# Hank.net
KiCad netlist of a schematic drawn in EAGLE
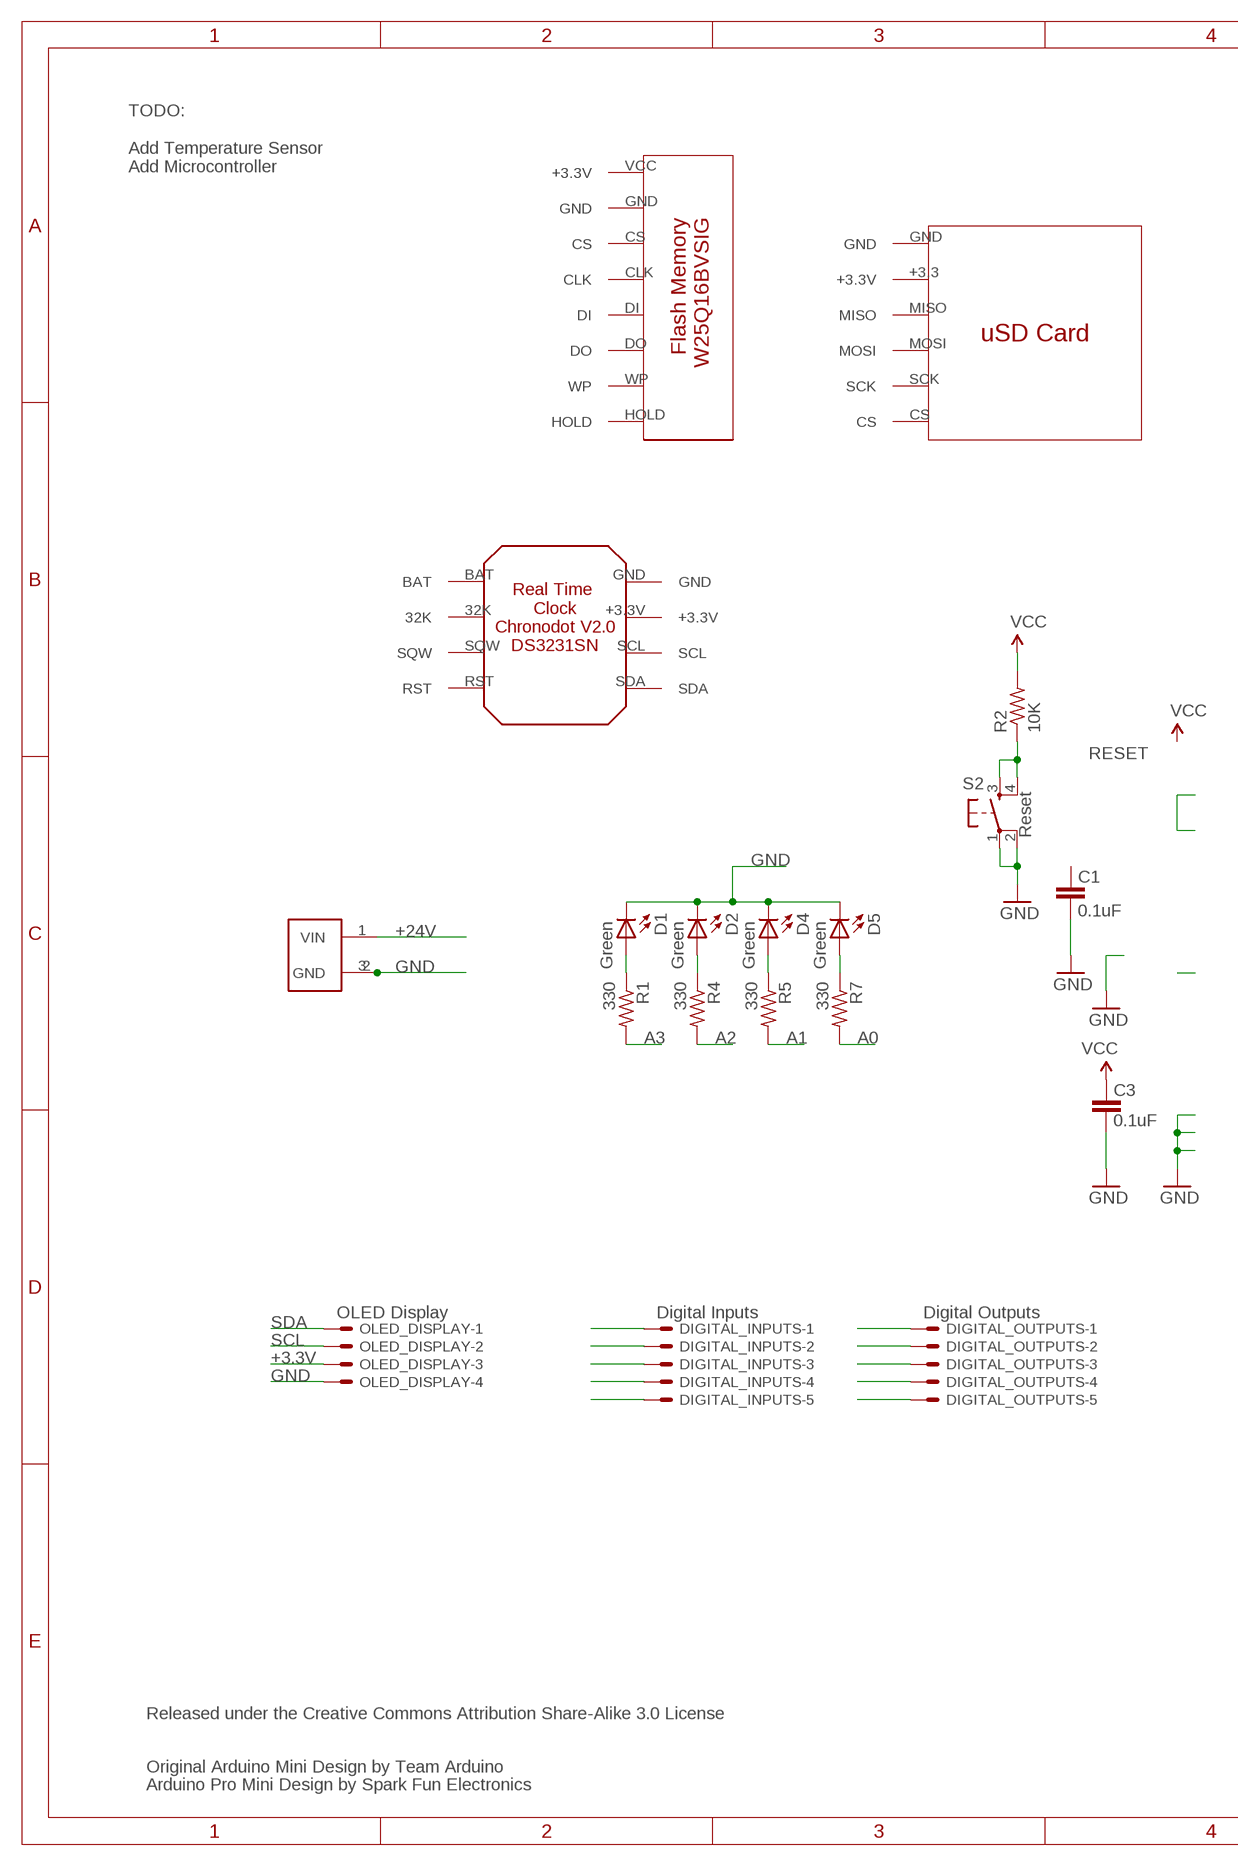
[diagram p0: schematic, sheet 1, part 1 of 2]
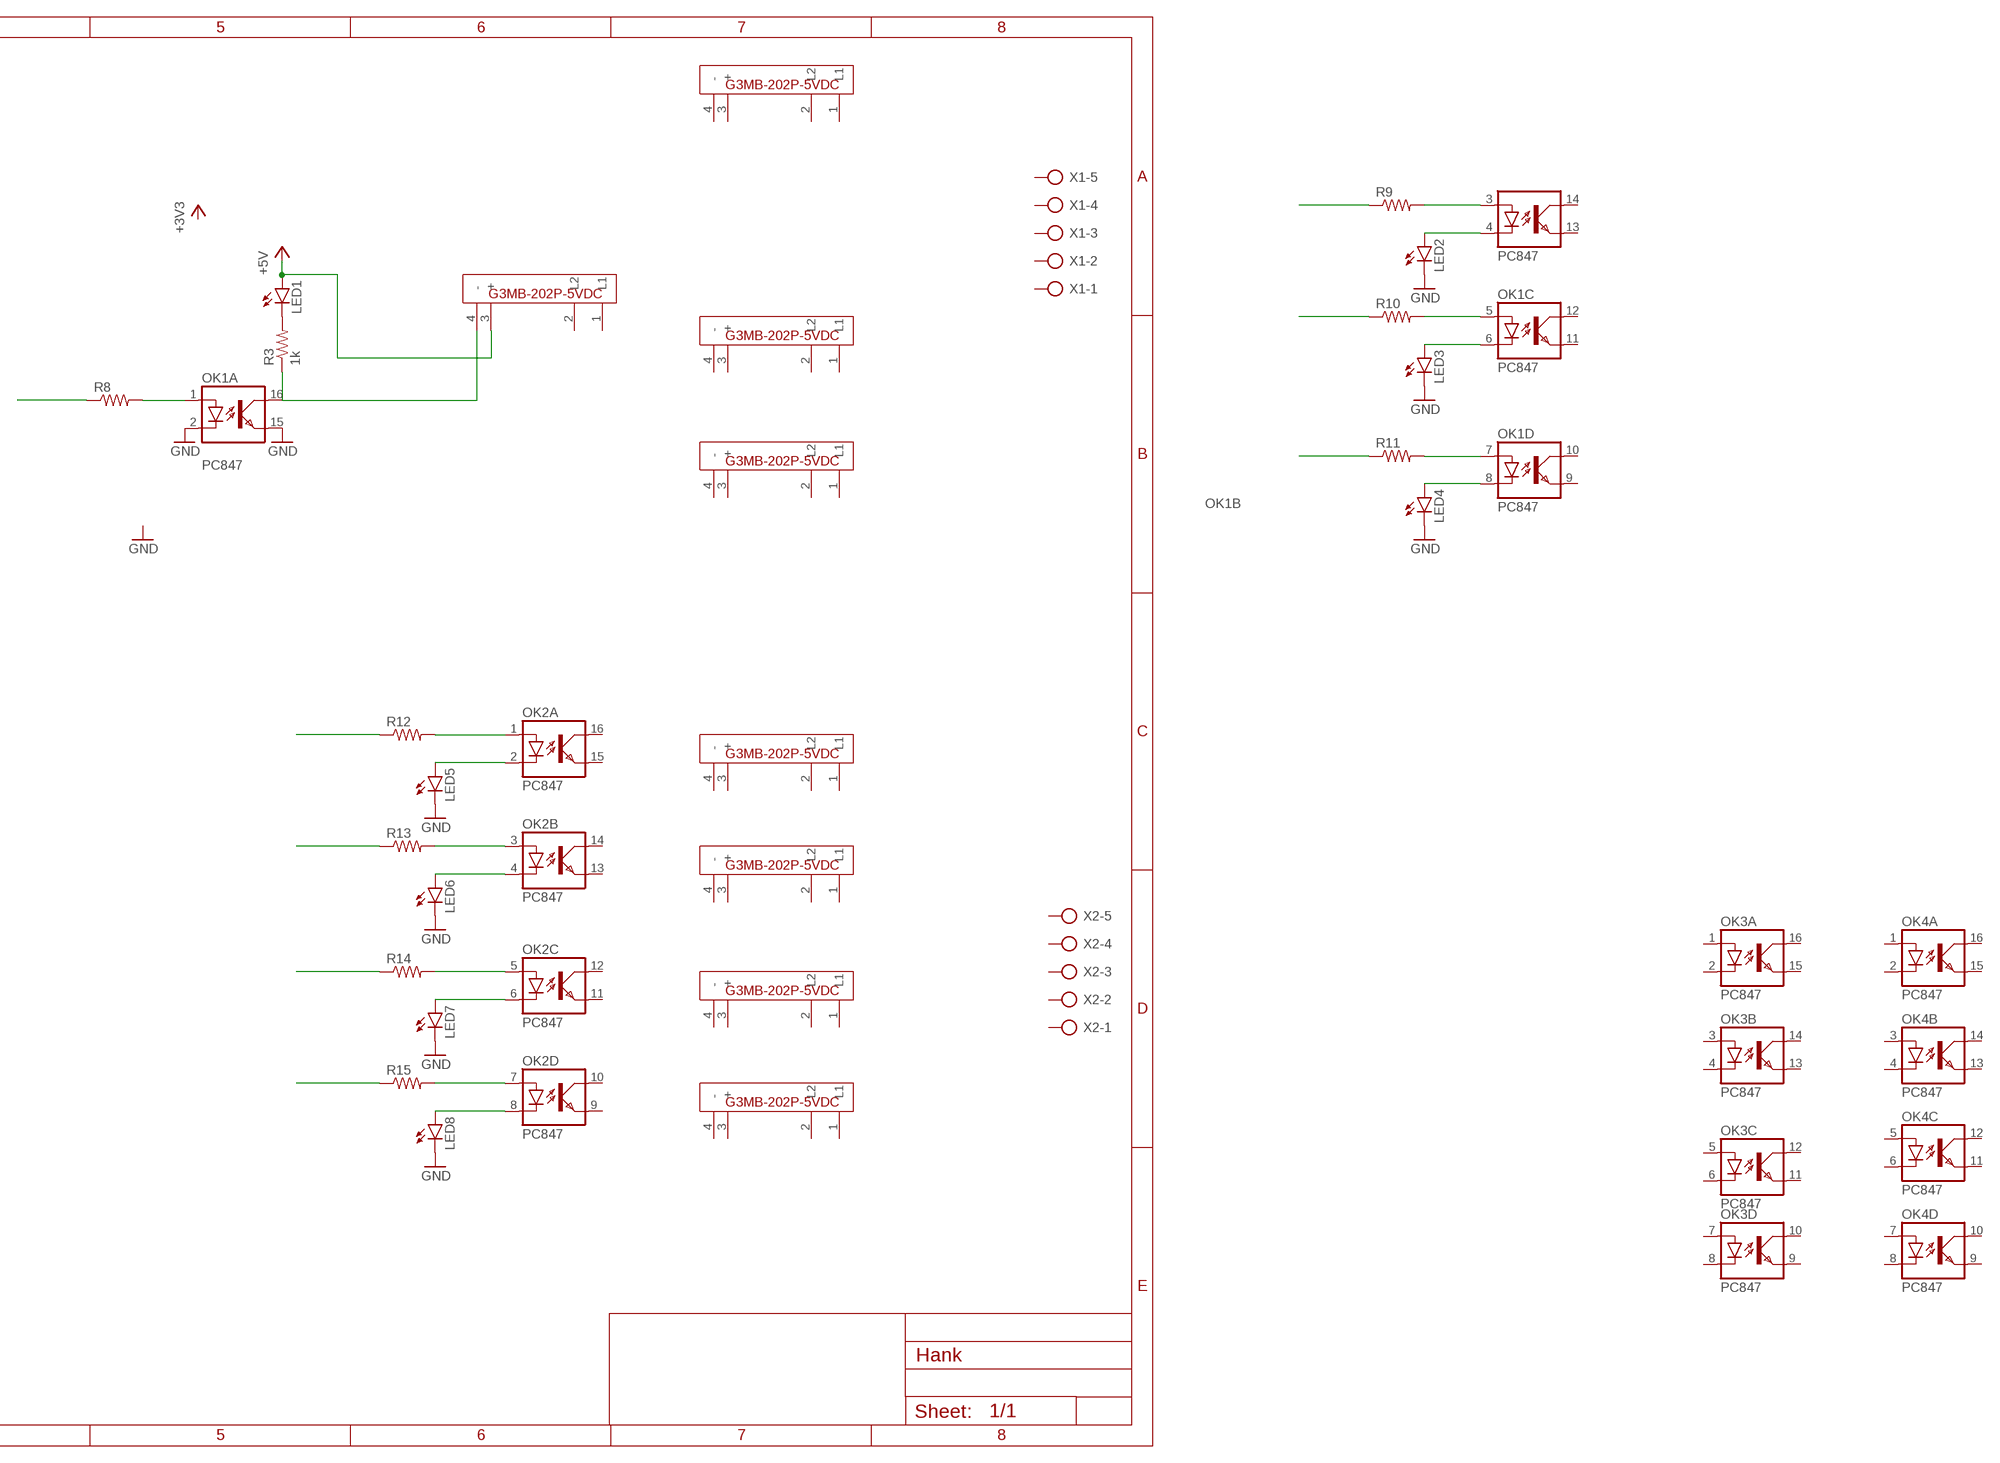
[diagram p1: schematic, sheet 1, part 2 of 2]

(export (version "E")
  (design (tool "Eeschema 10.0.6"))
  (components
    (comp (ref "C1")
      (value "0.1uF")
      (footprint "eagle-import:C0603")
      (libsource (lib "eagle-import") (part "C-EUC0603"))
    )
    (comp (ref "C3")
      (value "0.1uF")
      (footprint "eagle-import:C0603")
      (libsource (lib "eagle-import") (part "C-EUC0603"))
    )
    (comp (ref "D1")
      (value "Green")
      (footprint "eagle-import:LED-0603")
      (libsource (lib "eagle-import") (part "LED0603"))
    )
    (comp (ref "D2")
      (value "Green")
      (footprint "eagle-import:LED-0603")
      (libsource (lib "eagle-import") (part "LED0603"))
    )
    (comp (ref "D4")
      (value "Green")
      (footprint "eagle-import:LED-0603")
      (libsource (lib "eagle-import") (part "LED0603"))
    )
    (comp (ref "D5")
      (value "Green")
      (footprint "eagle-import:LED-0603")
      (libsource (lib "eagle-import") (part "LED0603"))
    )
    (comp (ref "DIGITAL_INPUTS")
      (value "Digital Inputs")
      (footprint "eagle-import:22-23-2051")
      (fields (field (name "MF") "MOLEX") (field (name "MPN") "22-23-2051"))
      (libsource (lib "eagle-import") (part "22-23-2051"))
    )
    (comp (ref "DIGITAL_OUTPUTS")
      (value "Digital Outputs")
      (footprint "eagle-import:22-23-2051")
      (fields (field (name "MF") "MOLEX") (field (name "MPN") "22-23-2051"))
      (libsource (lib "eagle-import") (part "22-23-2051"))
    )
    (comp (ref "LED1")
      (value "LED3MM")
      (footprint "eagle-import:LED3MM")
      (libsource (lib "eagle-import") (part "led_259_LED3MM"))
    )
    (comp (ref "LED2")
      (value "LED3MM")
      (footprint "eagle-import:LED3MM")
      (libsource (lib "eagle-import") (part "led_259_LED3MM"))
    )
    (comp (ref "LED3")
      (value "LED3MM")
      (footprint "eagle-import:LED3MM")
      (libsource (lib "eagle-import") (part "led_259_LED3MM"))
    )
    (comp (ref "LED4")
      (value "LED3MM")
      (footprint "eagle-import:LED3MM")
      (libsource (lib "eagle-import") (part "led_259_LED3MM"))
    )
    (comp (ref "LED5")
      (value "LED3MM")
      (footprint "eagle-import:LED3MM")
      (libsource (lib "eagle-import") (part "led_259_LED3MM"))
    )
    (comp (ref "LED6")
      (value "LED3MM")
      (footprint "eagle-import:LED3MM")
      (libsource (lib "eagle-import") (part "led_259_LED3MM"))
    )
    (comp (ref "LED7")
      (value "LED3MM")
      (footprint "eagle-import:LED3MM")
      (libsource (lib "eagle-import") (part "led_259_LED3MM"))
    )
    (comp (ref "LED8")
      (value "LED3MM")
      (footprint "eagle-import:LED3MM")
      (libsource (lib "eagle-import") (part "led_259_LED3MM"))
    )
    (comp (ref "OK1")
      (value "PC847")
      (footprint "eagle-import:DIL16")
      (libsource (lib "eagle-import") (part "PC847"))
    )
    (comp (ref "OK2")
      (value "PC847")
      (footprint "eagle-import:DIL16")
      (libsource (lib "eagle-import") (part "PC847"))
    )
    (comp (ref "OK3")
      (value "PC847")
      (footprint "eagle-import:DIL16")
      (libsource (lib "eagle-import") (part "PC847"))
    )
    (comp (ref "OK4")
      (value "PC847")
      (footprint "eagle-import:DIL16")
      (libsource (lib "eagle-import") (part "PC847"))
    )
    (comp (ref "OLED_DISPLAY")
      (value "OLED Display")
      (footprint "eagle-import:22-23-2041")
      (fields (field (name "MF") "MOLEX") (field (name "MPN") "22-23-2041"))
      (libsource (lib "eagle-import") (part "22-23-2041"))
    )
    (comp (ref "R1")
      (value "330")
      (footprint "eagle-import:R0603")
      (libsource (lib "eagle-import") (part "resistor_R-US_R0603"))
    )
    (comp (ref "R2")
      (value "10K")
      (footprint "eagle-import:R0603")
      (libsource (lib "eagle-import") (part "resistor_R-US_R0603"))
    )
    (comp (ref "R3")
      (value "1k")
      (footprint "eagle-import:0207_10")
      (libsource (lib "eagle-import") (part "R-US_0207/10"))
    )
    (comp (ref "R4")
      (value "330")
      (footprint "eagle-import:R0603")
      (libsource (lib "eagle-import") (part "resistor_R-US_R0603"))
    )
    (comp (ref "R5")
      (value "330")
      (footprint "eagle-import:R0603")
      (libsource (lib "eagle-import") (part "resistor_R-US_R0603"))
    )
    (comp (ref "R7")
      (value "330")
      (footprint "eagle-import:R0603")
      (libsource (lib "eagle-import") (part "resistor_R-US_R0603"))
    )
    (comp (ref "R8")
      (value "R-US_0207/10")
      (footprint "eagle-import:0207_10")
      (libsource (lib "eagle-import") (part "R-US_0207/10"))
    )
    (comp (ref "R9")
      (value "R-US_0207/10")
      (footprint "eagle-import:0207_10")
      (libsource (lib "eagle-import") (part "R-US_0207/10"))
    )
    (comp (ref "R10")
      (value "R-US_0207/10")
      (footprint "eagle-import:0207_10")
      (libsource (lib "eagle-import") (part "R-US_0207/10"))
    )
    (comp (ref "R11")
      (value "R-US_0207/10")
      (footprint "eagle-import:0207_10")
      (libsource (lib "eagle-import") (part "R-US_0207/10"))
    )
    (comp (ref "R12")
      (value "R-US_0207/10")
      (footprint "eagle-import:0207_10")
      (libsource (lib "eagle-import") (part "R-US_0207/10"))
    )
    (comp (ref "R13")
      (value "R-US_0207/10")
      (footprint "eagle-import:0207_10")
      (libsource (lib "eagle-import") (part "R-US_0207/10"))
    )
    (comp (ref "R14")
      (value "R-US_0207/10")
      (footprint "eagle-import:0207_10")
      (libsource (lib "eagle-import") (part "R-US_0207/10"))
    )
    (comp (ref "R15")
      (value "R-US_0207/10")
      (footprint "eagle-import:0207_10")
      (libsource (lib "eagle-import") (part "R-US_0207/10"))
    )
    (comp (ref "S2")
      (value "Reset")
      (footprint "eagle-import:TACTILE_SWITCH_SMD")
      (libsource (lib "eagle-import") (part "TAC_SWITCHSMD"))
    )
    (comp (ref "U$1")
      (value "SSR")
      (footprint "eagle-import:SSR_FOOTPRINT")
      (libsource (lib "eagle-import") (part "SSR"))
    )
    (comp (ref "U$3")
      (value "BARREL-3.5MM")
      (footprint "eagle-import:BARREL-3.5MM")
      (libsource (lib "eagle-import") (part "BARREL-3.5MM"))
    )
    (comp (ref "U$4")
      (value "FLASH_MEMORY")
      (footprint "eagle-import:FLASHMEMORY_FOOTPRINT")
      (libsource (lib "eagle-import") (part "FLASH_MEMORY"))
    )
    (comp (ref "U$6")
      (value "RTC")
      (footprint "eagle-import:RTC_FOOTPRINT")
      (libsource (lib "eagle-import") (part "RTC"))
    )
    (comp (ref "U$7")
      (value "SSR")
      (footprint "eagle-import:SSR_FOOTPRINT")
      (libsource (lib "eagle-import") (part "SSR"))
    )
    (comp (ref "U$8")
      (value "SSR")
      (footprint "eagle-import:SSR_FOOTPRINT")
      (libsource (lib "eagle-import") (part "SSR"))
    )
    (comp (ref "U$9")
      (value "SSR")
      (footprint "eagle-import:SSR_FOOTPRINT")
      (libsource (lib "eagle-import") (part "SSR"))
    )
    (comp (ref "U$10")
      (value "SSR")
      (footprint "eagle-import:SSR_FOOTPRINT")
      (libsource (lib "eagle-import") (part "SSR"))
    )
    (comp (ref "U$11")
      (value "SSR")
      (footprint "eagle-import:SSR_FOOTPRINT")
      (libsource (lib "eagle-import") (part "SSR"))
    )
    (comp (ref "U$12")
      (value "SSR")
      (footprint "eagle-import:SSR_FOOTPRINT")
      (libsource (lib "eagle-import") (part "SSR"))
    )
    (comp (ref "U$13")
      (value "SSR")
      (footprint "eagle-import:SSR_FOOTPRINT")
      (libsource (lib "eagle-import") (part "SSR"))
    )
    (comp (ref "U$14")
      (value "SD_CARD_READER")
      (footprint "eagle-import:SD_CARD_READER_FOOTPRINT")
      (libsource (lib "eagle-import") (part "SD_CARD_READER"))
    )
    (comp (ref "X1")
      (value "AK300/5")
      (footprint "eagle-import:AK300_5")
      (libsource (lib "eagle-import") (part "AK300/5"))
    )
    (comp (ref "X2")
      (value "AK300/5")
      (footprint "eagle-import:AK300_5")
      (libsource (lib "eagle-import") (part "AK300/5"))
    )
  )
  (nets
    (net (code "2") (name "+5V") (class "Default")
      (node (ref "LED1") (pin "A") (pinfunction "A_A") (pintype "passive"))
      (node (ref "U$7") (pin "3") (pinfunction "+_3") (pintype "bidirectional"))
    )
    (net (code "3") (name "/+3.3V") (class "Default")
      (node (ref "OLED_DISPLAY") (pin "3") (pinfunction "S_3") (pintype "passive"))
    )
    (net (code "4") (name "/+24V") (class "Default")
      (node (ref "U$3") (pin "1") (pinfunction "VIN_1") (pintype "bidirectional"))
    )
    (net (code "5") (name "/A0") (class "Default")
      (node (ref "R7") (pin "2") (pinfunction "2_2") (pintype "passive"))
    )
    (net (code "6") (name "/A1") (class "Default")
      (node (ref "R5") (pin "2") (pinfunction "2_2") (pintype "passive"))
    )
    (net (code "7") (name "/A2") (class "Default")
      (node (ref "R4") (pin "2") (pinfunction "2_2") (pintype "passive"))
    )
    (net (code "8") (name "/A3") (class "Default")
      (node (ref "R1") (pin "2") (pinfunction "2_2") (pintype "passive"))
    )
    (net (code "9") (name "/RESET") (class "Default")
      (node (ref "R2") (pin "1") (pinfunction "1_1") (pintype "passive"))
      (node (ref "S2") (pin "3") (pinfunction "3_3") (pintype "passive"))
      (node (ref "S2") (pin "4") (pinfunction "4_4") (pintype "passive"))
    )
    (net (code "10") (name "/SCL") (class "Default")
      (node (ref "OLED_DISPLAY") (pin "2") (pinfunction "S_2") (pintype "passive"))
    )
    (net (code "11") (name "/SDA") (class "Default")
      (node (ref "OLED_DISPLAY") (pin "1") (pinfunction "S_1") (pintype "passive"))
    )
    (net (code "12") (name "GND") (class "Default")
      (node (ref "C1") (pin "1") (pinfunction "1_1") (pintype "passive"))
      (node (ref "C3") (pin "1") (pinfunction "1_1") (pintype "passive"))
      (node (ref "D1") (pin "C") (pinfunction "C_C") (pintype "passive"))
      (node (ref "D2") (pin "C") (pinfunction "C_C") (pintype "passive"))
      (node (ref "D4") (pin "C") (pinfunction "C_C") (pintype "passive"))
      (node (ref "D5") (pin "C") (pinfunction "C_C") (pintype "passive"))
      (node (ref "LED2") (pin "K") (pinfunction "C_K") (pintype "passive"))
      (node (ref "LED3") (pin "K") (pinfunction "C_K") (pintype "passive"))
      (node (ref "LED4") (pin "K") (pinfunction "C_K") (pintype "passive"))
      (node (ref "LED5") (pin "K") (pinfunction "C_K") (pintype "passive"))
      (node (ref "LED6") (pin "K") (pinfunction "C_K") (pintype "passive"))
      (node (ref "LED7") (pin "K") (pinfunction "C_K") (pintype "passive"))
      (node (ref "LED8") (pin "K") (pinfunction "C_K") (pintype "passive"))
      (node (ref "OK1") (pin "15") (pinfunction "EMIT_15") (pintype "passive"))
      (node (ref "OK1") (pin "2") (pinfunction "C_2") (pintype "passive"))
      (node (ref "OLED_DISPLAY") (pin "4") (pinfunction "S_4") (pintype "passive"))
      (node (ref "S2") (pin "1") (pinfunction "1_1") (pintype "passive"))
      (node (ref "S2") (pin "2") (pinfunction "2_2") (pintype "passive"))
      (node (ref "U$3") (pin "2") (pinfunction "GND___2") (pintype "bidirectional"))
      (node (ref "U$3") (pin "3") (pinfunction "GND_3") (pintype "bidirectional"))
    )
    (net (code "13") (name "Net-(D1-PadA)") (class "Default")
      (node (ref "D1") (pin "A") (pinfunction "A_A") (pintype "passive"))
      (node (ref "R1") (pin "1") (pinfunction "1_1") (pintype "passive"))
    )
    (net (code "14") (name "Net-(D2-PadA)") (class "Default")
      (node (ref "D2") (pin "A") (pinfunction "A_A") (pintype "passive"))
      (node (ref "R4") (pin "1") (pinfunction "1_1") (pintype "passive"))
    )
    (net (code "15") (name "Net-(D4-PadA)") (class "Default")
      (node (ref "D4") (pin "A") (pinfunction "A_A") (pintype "passive"))
      (node (ref "R5") (pin "1") (pinfunction "1_1") (pintype "passive"))
    )
    (net (code "16") (name "Net-(D5-PadA)") (class "Default")
      (node (ref "D5") (pin "A") (pinfunction "A_A") (pintype "passive"))
      (node (ref "R7") (pin "1") (pinfunction "1_1") (pintype "passive"))
    )
    (net (code "17") (name "Net-(LED1-C)") (class "Default")
      (node (ref "LED1") (pin "K") (pinfunction "C_K") (pintype "passive"))
      (node (ref "R3") (pin "2") (pinfunction "2_2") (pintype "passive"))
    )
    (net (code "18") (name "Net-(OK1A-A)") (class "Default")
      (node (ref "OK1") (pin "1") (pinfunction "A_1") (pintype "passive"))
      (node (ref "R8") (pin "2") (pinfunction "2_2") (pintype "passive"))
    )
    (net (code "19") (name "Net-(OK1A-COL)") (class "Default")
      (node (ref "OK1") (pin "16") (pinfunction "COL_16") (pintype "passive"))
      (node (ref "R3") (pin "1") (pinfunction "1_1") (pintype "passive"))
      (node (ref "U$7") (pin "4") (pinfunction "-_4") (pintype "bidirectional"))
    )
    (net (code "20") (name "Net-(OK1B-A)") (class "Default")
      (node (ref "OK1") (pin "3") (pinfunction "A_3") (pintype "passive"))
      (node (ref "R9") (pin "2") (pinfunction "2_2") (pintype "passive"))
    )
    (net (code "21") (name "Net-(OK1B-C)") (class "Default")
      (node (ref "LED2") (pin "A") (pinfunction "A_A") (pintype "passive"))
      (node (ref "OK1") (pin "4") (pinfunction "C_4") (pintype "passive"))
    )
    (net (code "22") (name "Net-(OK1C-A)") (class "Default")
      (node (ref "OK1") (pin "5") (pinfunction "A_5") (pintype "passive"))
      (node (ref "R10") (pin "2") (pinfunction "2_2") (pintype "passive"))
    )
    (net (code "23") (name "Net-(OK1C-C)") (class "Default")
      (node (ref "LED3") (pin "A") (pinfunction "A_A") (pintype "passive"))
      (node (ref "OK1") (pin "6") (pinfunction "C_6") (pintype "passive"))
    )
    (net (code "24") (name "Net-(OK1D-A)") (class "Default")
      (node (ref "OK1") (pin "7") (pinfunction "A_7") (pintype "passive"))
      (node (ref "R11") (pin "2") (pinfunction "2_2") (pintype "passive"))
    )
    (net (code "25") (name "Net-(OK1D-C)") (class "Default")
      (node (ref "LED4") (pin "A") (pinfunction "A_A") (pintype "passive"))
      (node (ref "OK1") (pin "8") (pinfunction "C_8") (pintype "passive"))
    )
    (net (code "26") (name "Net-(OK2A-A)") (class "Default")
      (node (ref "OK2") (pin "1") (pinfunction "A_1") (pintype "passive"))
      (node (ref "R12") (pin "2") (pinfunction "2_2") (pintype "passive"))
    )
    (net (code "27") (name "Net-(OK2A-C)") (class "Default")
      (node (ref "LED5") (pin "A") (pinfunction "A_A") (pintype "passive"))
      (node (ref "OK2") (pin "2") (pinfunction "C_2") (pintype "passive"))
    )
    (net (code "28") (name "Net-(OK2B-A)") (class "Default")
      (node (ref "OK2") (pin "3") (pinfunction "A_3") (pintype "passive"))
      (node (ref "R13") (pin "2") (pinfunction "2_2") (pintype "passive"))
    )
    (net (code "29") (name "Net-(OK2B-C)") (class "Default")
      (node (ref "LED6") (pin "A") (pinfunction "A_A") (pintype "passive"))
      (node (ref "OK2") (pin "4") (pinfunction "C_4") (pintype "passive"))
    )
    (net (code "30") (name "Net-(OK2C-A)") (class "Default")
      (node (ref "OK2") (pin "5") (pinfunction "A_5") (pintype "passive"))
      (node (ref "R14") (pin "2") (pinfunction "2_2") (pintype "passive"))
    )
    (net (code "31") (name "Net-(OK2C-C)") (class "Default")
      (node (ref "LED7") (pin "A") (pinfunction "A_A") (pintype "passive"))
      (node (ref "OK2") (pin "6") (pinfunction "C_6") (pintype "passive"))
    )
    (net (code "32") (name "Net-(OK2D-A)") (class "Default")
      (node (ref "OK2") (pin "7") (pinfunction "A_7") (pintype "passive"))
      (node (ref "R15") (pin "2") (pinfunction "2_2") (pintype "passive"))
    )
    (net (code "33") (name "Net-(OK2D-C)") (class "Default")
      (node (ref "LED8") (pin "A") (pinfunction "A_A") (pintype "passive"))
      (node (ref "OK2") (pin "8") (pinfunction "C_8") (pintype "passive"))
    )
    (net (code "34") (name "VCC") (class "Default")
      (node (ref "C3") (pin "2") (pinfunction "2_2") (pintype "passive"))
      (node (ref "R2") (pin "2") (pinfunction "2_2") (pintype "passive"))
    )
    (net (code "35") (name "unconnected-(C1-Pad2)") (class "Default")
      (node (ref "C1") (pin "2") (pinfunction "2_2") (pintype "passive"))
    )
    (net (code "36") (name "unconnected-(DIGITAL_INPUTSA-S-Pad1)") (class "Default")
      (node (ref "DIGITAL_INPUTS") (pin "1") (pinfunction "S_1") (pintype "passive"))
    )
    (net (code "37") (name "unconnected-(DIGITAL_INPUTSB-S-Pad2)") (class "Default")
      (node (ref "DIGITAL_INPUTS") (pin "2") (pinfunction "S_2") (pintype "passive"))
    )
    (net (code "38") (name "unconnected-(DIGITAL_INPUTSC-S-Pad3)") (class "Default")
      (node (ref "DIGITAL_INPUTS") (pin "3") (pinfunction "S_3") (pintype "passive"))
    )
    (net (code "39") (name "unconnected-(DIGITAL_INPUTSD-S-Pad4)") (class "Default")
      (node (ref "DIGITAL_INPUTS") (pin "4") (pinfunction "S_4") (pintype "passive"))
    )
    (net (code "40") (name "unconnected-(DIGITAL_INPUTSE-S-Pad5)") (class "Default")
      (node (ref "DIGITAL_INPUTS") (pin "5") (pinfunction "S_5") (pintype "passive"))
    )
    (net (code "41") (name "unconnected-(DIGITAL_OUTPUTSA-S-Pad1)") (class "Default")
      (node (ref "DIGITAL_OUTPUTS") (pin "1") (pinfunction "S_1") (pintype "passive"))
    )
    (net (code "42") (name "unconnected-(DIGITAL_OUTPUTSB-S-Pad2)") (class "Default")
      (node (ref "DIGITAL_OUTPUTS") (pin "2") (pinfunction "S_2") (pintype "passive"))
    )
    (net (code "43") (name "unconnected-(DIGITAL_OUTPUTSC-S-Pad3)") (class "Default")
      (node (ref "DIGITAL_OUTPUTS") (pin "3") (pinfunction "S_3") (pintype "passive"))
    )
    (net (code "44") (name "unconnected-(DIGITAL_OUTPUTSD-S-Pad4)") (class "Default")
      (node (ref "DIGITAL_OUTPUTS") (pin "4") (pinfunction "S_4") (pintype "passive"))
    )
    (net (code "45") (name "unconnected-(DIGITAL_OUTPUTSE-S-Pad5)") (class "Default")
      (node (ref "DIGITAL_OUTPUTS") (pin "5") (pinfunction "S_5") (pintype "passive"))
    )
    (net (code "46") (name "unconnected-(OK1B-COL-Pad14)") (class "Default")
      (node (ref "OK1") (pin "14") (pinfunction "COL_14") (pintype "passive"))
    )
    (net (code "47") (name "unconnected-(OK1B-EMIT-Pad13)") (class "Default")
      (node (ref "OK1") (pin "13") (pinfunction "EMIT_13") (pintype "passive"))
    )
    (net (code "48") (name "unconnected-(OK1C-COL-Pad12)") (class "Default")
      (node (ref "OK1") (pin "12") (pinfunction "COL_12") (pintype "passive"))
    )
    (net (code "49") (name "unconnected-(OK1C-EMIT-Pad11)") (class "Default")
      (node (ref "OK1") (pin "11") (pinfunction "EMIT_11") (pintype "passive"))
    )
    (net (code "50") (name "unconnected-(OK1D-COL-Pad10)") (class "Default")
      (node (ref "OK1") (pin "10") (pinfunction "COL_10") (pintype "passive"))
    )
    (net (code "51") (name "unconnected-(OK1D-EMIT-Pad9)") (class "Default")
      (node (ref "OK1") (pin "9") (pinfunction "EMIT_9") (pintype "passive"))
    )
    (net (code "52") (name "unconnected-(OK2A-COL-Pad16)") (class "Default")
      (node (ref "OK2") (pin "16") (pinfunction "COL_16") (pintype "passive"))
    )
    (net (code "53") (name "unconnected-(OK2A-EMIT-Pad15)") (class "Default")
      (node (ref "OK2") (pin "15") (pinfunction "EMIT_15") (pintype "passive"))
    )
    (net (code "54") (name "unconnected-(OK2B-COL-Pad14)") (class "Default")
      (node (ref "OK2") (pin "14") (pinfunction "COL_14") (pintype "passive"))
    )
    (net (code "55") (name "unconnected-(OK2B-EMIT-Pad13)") (class "Default")
      (node (ref "OK2") (pin "13") (pinfunction "EMIT_13") (pintype "passive"))
    )
    (net (code "56") (name "unconnected-(OK2C-COL-Pad12)") (class "Default")
      (node (ref "OK2") (pin "12") (pinfunction "COL_12") (pintype "passive"))
    )
    (net (code "57") (name "unconnected-(OK2C-EMIT-Pad11)") (class "Default")
      (node (ref "OK2") (pin "11") (pinfunction "EMIT_11") (pintype "passive"))
    )
    (net (code "58") (name "unconnected-(OK2D-COL-Pad10)") (class "Default")
      (node (ref "OK2") (pin "10") (pinfunction "COL_10") (pintype "passive"))
    )
    (net (code "59") (name "unconnected-(OK2D-EMIT-Pad9)") (class "Default")
      (node (ref "OK2") (pin "9") (pinfunction "EMIT_9") (pintype "passive"))
    )
    (net (code "60") (name "unconnected-(OK3A-A-Pad1)") (class "Default")
      (node (ref "OK3") (pin "1") (pinfunction "A_1") (pintype "passive"))
    )
    (net (code "61") (name "unconnected-(OK3A-C-Pad2)") (class "Default")
      (node (ref "OK3") (pin "2") (pinfunction "C_2") (pintype "passive"))
    )
    (net (code "62") (name "unconnected-(OK3A-COL-Pad16)") (class "Default")
      (node (ref "OK3") (pin "16") (pinfunction "COL_16") (pintype "passive"))
    )
    (net (code "63") (name "unconnected-(OK3A-EMIT-Pad15)") (class "Default")
      (node (ref "OK3") (pin "15") (pinfunction "EMIT_15") (pintype "passive"))
    )
    (net (code "64") (name "unconnected-(OK3B-A-Pad3)") (class "Default")
      (node (ref "OK3") (pin "3") (pinfunction "A_3") (pintype "passive"))
    )
    (net (code "65") (name "unconnected-(OK3B-C-Pad4)") (class "Default")
      (node (ref "OK3") (pin "4") (pinfunction "C_4") (pintype "passive"))
    )
    (net (code "66") (name "unconnected-(OK3B-COL-Pad14)") (class "Default")
      (node (ref "OK3") (pin "14") (pinfunction "COL_14") (pintype "passive"))
    )
    (net (code "67") (name "unconnected-(OK3B-EMIT-Pad13)") (class "Default")
      (node (ref "OK3") (pin "13") (pinfunction "EMIT_13") (pintype "passive"))
    )
    (net (code "68") (name "unconnected-(OK3C-A-Pad5)") (class "Default")
      (node (ref "OK3") (pin "5") (pinfunction "A_5") (pintype "passive"))
    )
    (net (code "69") (name "unconnected-(OK3C-C-Pad6)") (class "Default")
      (node (ref "OK3") (pin "6") (pinfunction "C_6") (pintype "passive"))
    )
    (net (code "70") (name "unconnected-(OK3C-COL-Pad12)") (class "Default")
      (node (ref "OK3") (pin "12") (pinfunction "COL_12") (pintype "passive"))
    )
    (net (code "71") (name "unconnected-(OK3C-EMIT-Pad11)") (class "Default")
      (node (ref "OK3") (pin "11") (pinfunction "EMIT_11") (pintype "passive"))
    )
    (net (code "72") (name "unconnected-(OK3D-A-Pad7)") (class "Default")
      (node (ref "OK3") (pin "7") (pinfunction "A_7") (pintype "passive"))
    )
    (net (code "73") (name "unconnected-(OK3D-C-Pad8)") (class "Default")
      (node (ref "OK3") (pin "8") (pinfunction "C_8") (pintype "passive"))
    )
    (net (code "74") (name "unconnected-(OK3D-COL-Pad10)") (class "Default")
      (node (ref "OK3") (pin "10") (pinfunction "COL_10") (pintype "passive"))
    )
    (net (code "75") (name "unconnected-(OK3D-EMIT-Pad9)") (class "Default")
      (node (ref "OK3") (pin "9") (pinfunction "EMIT_9") (pintype "passive"))
    )
    (net (code "76") (name "unconnected-(OK4A-A-Pad1)") (class "Default")
      (node (ref "OK4") (pin "1") (pinfunction "A_1") (pintype "passive"))
    )
    (net (code "77") (name "unconnected-(OK4A-C-Pad2)") (class "Default")
      (node (ref "OK4") (pin "2") (pinfunction "C_2") (pintype "passive"))
    )
    (net (code "78") (name "unconnected-(OK4A-COL-Pad16)") (class "Default")
      (node (ref "OK4") (pin "16") (pinfunction "COL_16") (pintype "passive"))
    )
    (net (code "79") (name "unconnected-(OK4A-EMIT-Pad15)") (class "Default")
      (node (ref "OK4") (pin "15") (pinfunction "EMIT_15") (pintype "passive"))
    )
    (net (code "80") (name "unconnected-(OK4B-A-Pad3)") (class "Default")
      (node (ref "OK4") (pin "3") (pinfunction "A_3") (pintype "passive"))
    )
    (net (code "81") (name "unconnected-(OK4B-C-Pad4)") (class "Default")
      (node (ref "OK4") (pin "4") (pinfunction "C_4") (pintype "passive"))
    )
    (net (code "82") (name "unconnected-(OK4B-COL-Pad14)") (class "Default")
      (node (ref "OK4") (pin "14") (pinfunction "COL_14") (pintype "passive"))
    )
    (net (code "83") (name "unconnected-(OK4B-EMIT-Pad13)") (class "Default")
      (node (ref "OK4") (pin "13") (pinfunction "EMIT_13") (pintype "passive"))
    )
    (net (code "84") (name "unconnected-(OK4C-A-Pad5)") (class "Default")
      (node (ref "OK4") (pin "5") (pinfunction "A_5") (pintype "passive"))
    )
    (net (code "85") (name "unconnected-(OK4C-C-Pad6)") (class "Default")
      (node (ref "OK4") (pin "6") (pinfunction "C_6") (pintype "passive"))
    )
    (net (code "86") (name "unconnected-(OK4C-COL-Pad12)") (class "Default")
      (node (ref "OK4") (pin "12") (pinfunction "COL_12") (pintype "passive"))
    )
    (net (code "87") (name "unconnected-(OK4C-EMIT-Pad11)") (class "Default")
      (node (ref "OK4") (pin "11") (pinfunction "EMIT_11") (pintype "passive"))
    )
    (net (code "88") (name "unconnected-(OK4D-A-Pad7)") (class "Default")
      (node (ref "OK4") (pin "7") (pinfunction "A_7") (pintype "passive"))
    )
    (net (code "89") (name "unconnected-(OK4D-C-Pad8)") (class "Default")
      (node (ref "OK4") (pin "8") (pinfunction "C_8") (pintype "passive"))
    )
    (net (code "90") (name "unconnected-(OK4D-COL-Pad10)") (class "Default")
      (node (ref "OK4") (pin "10") (pinfunction "COL_10") (pintype "passive"))
    )
    (net (code "91") (name "unconnected-(OK4D-EMIT-Pad9)") (class "Default")
      (node (ref "OK4") (pin "9") (pinfunction "EMIT_9") (pintype "passive"))
    )
    (net (code "92") (name "unconnected-(R8-Pad1)") (class "Default")
      (node (ref "R8") (pin "1") (pinfunction "1_1") (pintype "passive"))
    )
    (net (code "93") (name "unconnected-(R9-Pad1)") (class "Default")
      (node (ref "R9") (pin "1") (pinfunction "1_1") (pintype "passive"))
    )
    (net (code "94") (name "unconnected-(R10-Pad1)") (class "Default")
      (node (ref "R10") (pin "1") (pinfunction "1_1") (pintype "passive"))
    )
    (net (code "95") (name "unconnected-(R11-Pad1)") (class "Default")
      (node (ref "R11") (pin "1") (pinfunction "1_1") (pintype "passive"))
    )
    (net (code "96") (name "unconnected-(R12-Pad1)") (class "Default")
      (node (ref "R12") (pin "1") (pinfunction "1_1") (pintype "passive"))
    )
    (net (code "97") (name "unconnected-(R13-Pad1)") (class "Default")
      (node (ref "R13") (pin "1") (pinfunction "1_1") (pintype "passive"))
    )
    (net (code "98") (name "unconnected-(R14-Pad1)") (class "Default")
      (node (ref "R14") (pin "1") (pinfunction "1_1") (pintype "passive"))
    )
    (net (code "99") (name "unconnected-(R15-Pad1)") (class "Default")
      (node (ref "R15") (pin "1") (pinfunction "1_1") (pintype "passive"))
    )
    (net (code "100") (name "unconnected-(U$1-+-Pad3)") (class "Default")
      (node (ref "U$1") (pin "3") (pinfunction "+_3") (pintype "bidirectional"))
    )
    (net (code "101") (name "unconnected-(U$1---Pad4)") (class "Default")
      (node (ref "U$1") (pin "4") (pinfunction "-_4") (pintype "bidirectional"))
    )
    (net (code "102") (name "unconnected-(U$1-L1-Pad1)") (class "Default")
      (node (ref "U$1") (pin "1") (pinfunction "L1_1") (pintype "bidirectional"))
    )
    (net (code "103") (name "unconnected-(U$1-L2-Pad2)") (class "Default")
      (node (ref "U$1") (pin "2") (pinfunction "L2_2") (pintype "bidirectional"))
    )
    (net (code "104") (name "unconnected-(U$4-+3.3V-PadVCC)") (class "Default")
      (node (ref "U$4") (pin "VCC") (pinfunction "+3.3V_VCC") (pintype "bidirectional"))
    )
    (net (code "105") (name "unconnected-(U$4-PadCLK)") (class "Default")
      (node (ref "U$4") (pin "CLK") (pinfunction "CLK_CLK") (pintype "bidirectional"))
    )
    (net (code "106") (name "unconnected-(U$4-PadCS)") (class "Default")
      (node (ref "U$4") (pin "CS") (pinfunction "CS_CS") (pintype "bidirectional"))
    )
    (net (code "107") (name "unconnected-(U$4-PadDI)") (class "Default")
      (node (ref "U$4") (pin "DI") (pinfunction "DI_DI") (pintype "bidirectional"))
    )
    (net (code "108") (name "unconnected-(U$4-PadDO)") (class "Default")
      (node (ref "U$4") (pin "DO") (pinfunction "DO_DO") (pintype "bidirectional"))
    )
    (net (code "109") (name "unconnected-(U$4-PadGND)") (class "Default")
      (node (ref "U$4") (pin "GND") (pinfunction "GND_GND") (pintype "bidirectional"))
    )
    (net (code "110") (name "unconnected-(U$4-PadHOLD)") (class "Default")
      (node (ref "U$4") (pin "HOLD") (pinfunction "HOLD_HOLD") (pintype "bidirectional"))
    )
    (net (code "111") (name "unconnected-(U$4-PadWP)") (class "Default")
      (node (ref "U$4") (pin "WP") (pinfunction "WP_WP") (pintype "bidirectional"))
    )
    (net (code "112") (name "unconnected-(U$6-Pad+3.3V)") (class "Default")
      (node (ref "U$6") (pin "+3.3V") (pinfunction "+3.3V_+3.3V") (pintype "bidirectional"))
    )
    (net (code "113") (name "unconnected-(U$6-Pad32K)") (class "Default")
      (node (ref "U$6") (pin "32K") (pinfunction "32K_32K") (pintype "bidirectional"))
    )
    (net (code "114") (name "unconnected-(U$6-PadBAT)") (class "Default")
      (node (ref "U$6") (pin "BAT") (pinfunction "BAT_BAT") (pintype "bidirectional"))
    )
    (net (code "115") (name "unconnected-(U$6-PadGND)") (class "Default")
      (node (ref "U$6") (pin "GND") (pinfunction "GND_GND") (pintype "bidirectional"))
    )
    (net (code "116") (name "unconnected-(U$6-PadRST)") (class "Default")
      (node (ref "U$6") (pin "RST") (pinfunction "RST_RST") (pintype "bidirectional"))
    )
    (net (code "117") (name "unconnected-(U$6-PadSCL)") (class "Default")
      (node (ref "U$6") (pin "SCL") (pinfunction "SCL_SCL") (pintype "bidirectional"))
    )
    (net (code "118") (name "unconnected-(U$6-PadSDA)") (class "Default")
      (node (ref "U$6") (pin "SDA") (pinfunction "SDA_SDA") (pintype "bidirectional"))
    )
    (net (code "119") (name "unconnected-(U$6-PadSQW)") (class "Default")
      (node (ref "U$6") (pin "SQW") (pinfunction "SQW_SQW") (pintype "bidirectional"))
    )
    (net (code "120") (name "unconnected-(U$7-L1-Pad1)") (class "Default")
      (node (ref "U$7") (pin "1") (pinfunction "L1_1") (pintype "bidirectional"))
    )
    (net (code "121") (name "unconnected-(U$7-L2-Pad2)") (class "Default")
      (node (ref "U$7") (pin "2") (pinfunction "L2_2") (pintype "bidirectional"))
    )
    (net (code "122") (name "unconnected-(U$8-+-Pad3)") (class "Default")
      (node (ref "U$8") (pin "3") (pinfunction "+_3") (pintype "bidirectional"))
    )
    (net (code "123") (name "unconnected-(U$8---Pad4)") (class "Default")
      (node (ref "U$8") (pin "4") (pinfunction "-_4") (pintype "bidirectional"))
    )
    (net (code "124") (name "unconnected-(U$8-L1-Pad1)") (class "Default")
      (node (ref "U$8") (pin "1") (pinfunction "L1_1") (pintype "bidirectional"))
    )
    (net (code "125") (name "unconnected-(U$8-L2-Pad2)") (class "Default")
      (node (ref "U$8") (pin "2") (pinfunction "L2_2") (pintype "bidirectional"))
    )
    (net (code "126") (name "unconnected-(U$9-+-Pad3)") (class "Default")
      (node (ref "U$9") (pin "3") (pinfunction "+_3") (pintype "bidirectional"))
    )
    (net (code "127") (name "unconnected-(U$9---Pad4)") (class "Default")
      (node (ref "U$9") (pin "4") (pinfunction "-_4") (pintype "bidirectional"))
    )
    (net (code "128") (name "unconnected-(U$9-L1-Pad1)") (class "Default")
      (node (ref "U$9") (pin "1") (pinfunction "L1_1") (pintype "bidirectional"))
    )
    (net (code "129") (name "unconnected-(U$9-L2-Pad2)") (class "Default")
      (node (ref "U$9") (pin "2") (pinfunction "L2_2") (pintype "bidirectional"))
    )
    (net (code "130") (name "unconnected-(U$10-+-Pad3)") (class "Default")
      (node (ref "U$10") (pin "3") (pinfunction "+_3") (pintype "bidirectional"))
    )
    (net (code "131") (name "unconnected-(U$10---Pad4)") (class "Default")
      (node (ref "U$10") (pin "4") (pinfunction "-_4") (pintype "bidirectional"))
    )
    (net (code "132") (name "unconnected-(U$10-L1-Pad1)") (class "Default")
      (node (ref "U$10") (pin "1") (pinfunction "L1_1") (pintype "bidirectional"))
    )
    (net (code "133") (name "unconnected-(U$10-L2-Pad2)") (class "Default")
      (node (ref "U$10") (pin "2") (pinfunction "L2_2") (pintype "bidirectional"))
    )
    (net (code "134") (name "unconnected-(U$11-+-Pad3)") (class "Default")
      (node (ref "U$11") (pin "3") (pinfunction "+_3") (pintype "bidirectional"))
    )
    (net (code "135") (name "unconnected-(U$11---Pad4)") (class "Default")
      (node (ref "U$11") (pin "4") (pinfunction "-_4") (pintype "bidirectional"))
    )
    (net (code "136") (name "unconnected-(U$11-L1-Pad1)") (class "Default")
      (node (ref "U$11") (pin "1") (pinfunction "L1_1") (pintype "bidirectional"))
    )
    (net (code "137") (name "unconnected-(U$11-L2-Pad2)") (class "Default")
      (node (ref "U$11") (pin "2") (pinfunction "L2_2") (pintype "bidirectional"))
    )
    (net (code "138") (name "unconnected-(U$12-+-Pad3)") (class "Default")
      (node (ref "U$12") (pin "3") (pinfunction "+_3") (pintype "bidirectional"))
    )
    (net (code "139") (name "unconnected-(U$12---Pad4)") (class "Default")
      (node (ref "U$12") (pin "4") (pinfunction "-_4") (pintype "bidirectional"))
    )
    (net (code "140") (name "unconnected-(U$12-L1-Pad1)") (class "Default")
      (node (ref "U$12") (pin "1") (pinfunction "L1_1") (pintype "bidirectional"))
    )
    (net (code "141") (name "unconnected-(U$12-L2-Pad2)") (class "Default")
      (node (ref "U$12") (pin "2") (pinfunction "L2_2") (pintype "bidirectional"))
    )
    (net (code "142") (name "unconnected-(U$13-+-Pad3)") (class "Default")
      (node (ref "U$13") (pin "3") (pinfunction "+_3") (pintype "bidirectional"))
    )
    (net (code "143") (name "unconnected-(U$13---Pad4)") (class "Default")
      (node (ref "U$13") (pin "4") (pinfunction "-_4") (pintype "bidirectional"))
    )
    (net (code "144") (name "unconnected-(U$13-L1-Pad1)") (class "Default")
      (node (ref "U$13") (pin "1") (pinfunction "L1_1") (pintype "bidirectional"))
    )
    (net (code "145") (name "unconnected-(U$13-L2-Pad2)") (class "Default")
      (node (ref "U$13") (pin "2") (pinfunction "L2_2") (pintype "bidirectional"))
    )
    (net (code "146") (name "unconnected-(U$14-+3.3V-Pad+3.3)") (class "Default")
      (node (ref "U$14") (pin "+3.3") (pinfunction "+3.3V_+3.3") (pintype "bidirectional"))
    )
    (net (code "147") (name "unconnected-(U$14-PadCS)") (class "Default")
      (node (ref "U$14") (pin "CS") (pinfunction "CS_CS") (pintype "bidirectional"))
    )
    (net (code "148") (name "unconnected-(U$14-PadGND)") (class "Default")
      (node (ref "U$14") (pin "GND") (pinfunction "GND_GND") (pintype "bidirectional"))
    )
    (net (code "149") (name "unconnected-(U$14-PadMISO)") (class "Default")
      (node (ref "U$14") (pin "MISO") (pinfunction "MISO_MISO") (pintype "bidirectional"))
    )
    (net (code "150") (name "unconnected-(U$14-PadMOSI)") (class "Default")
      (node (ref "U$14") (pin "MOSI") (pinfunction "MOSI_MOSI") (pintype "bidirectional"))
    )
    (net (code "151") (name "unconnected-(U$14-PadSCK)") (class "Default")
      (node (ref "U$14") (pin "SCK") (pinfunction "SCK_SCK") (pintype "bidirectional"))
    )
    (net (code "152") (name "unconnected-(X1A-KL-Pad1)") (class "Default")
      (node (ref "X1") (pin "1") (pinfunction "KL_1") (pintype "passive"))
    )
    (net (code "153") (name "unconnected-(X1B-KL-Pad2)") (class "Default")
      (node (ref "X1") (pin "2") (pinfunction "KL_2") (pintype "passive"))
    )
    (net (code "154") (name "unconnected-(X1C-KL-Pad3)") (class "Default")
      (node (ref "X1") (pin "3") (pinfunction "KL_3") (pintype "passive"))
    )
    (net (code "155") (name "unconnected-(X1D-KL-Pad4)") (class "Default")
      (node (ref "X1") (pin "4") (pinfunction "KL_4") (pintype "passive"))
    )
    (net (code "156") (name "unconnected-(X1E-KL-Pad5)") (class "Default")
      (node (ref "X1") (pin "5") (pinfunction "KL_5") (pintype "passive"))
    )
    (net (code "157") (name "unconnected-(X2A-KL-Pad1)") (class "Default")
      (node (ref "X2") (pin "1") (pinfunction "KL_1") (pintype "passive"))
    )
    (net (code "158") (name "unconnected-(X2B-KL-Pad2)") (class "Default")
      (node (ref "X2") (pin "2") (pinfunction "KL_2") (pintype "passive"))
    )
    (net (code "159") (name "unconnected-(X2C-KL-Pad3)") (class "Default")
      (node (ref "X2") (pin "3") (pinfunction "KL_3") (pintype "passive"))
    )
    (net (code "160") (name "unconnected-(X2D-KL-Pad4)") (class "Default")
      (node (ref "X2") (pin "4") (pinfunction "KL_4") (pintype "passive"))
    )
    (net (code "161") (name "unconnected-(X2E-KL-Pad5)") (class "Default")
      (node (ref "X2") (pin "5") (pinfunction "KL_5") (pintype "passive"))
    )
  )
)
